# RPi-HAT_BUS-Controller_V0_3.net
KiCad netlist of a schematic drawn in EAGLE
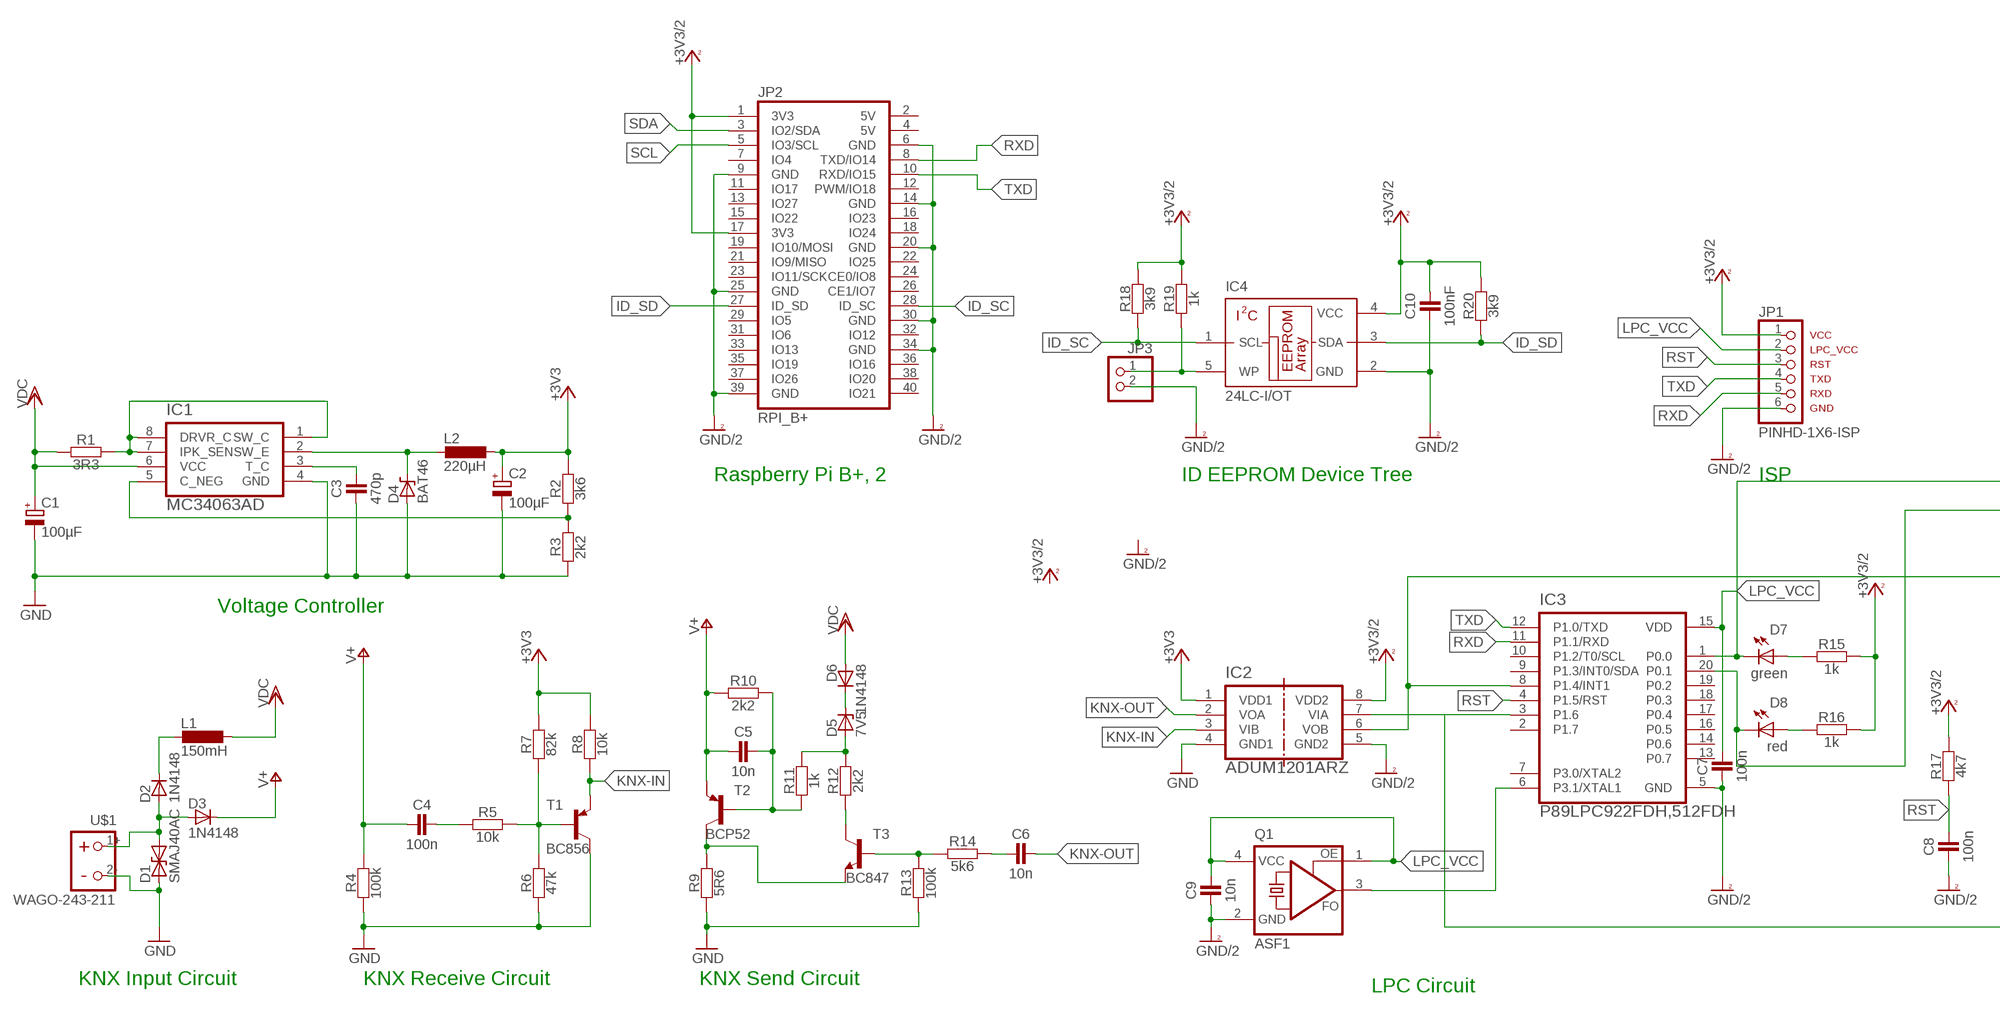
[diagram p0: schematic, sheet 1, part 1 of 2]
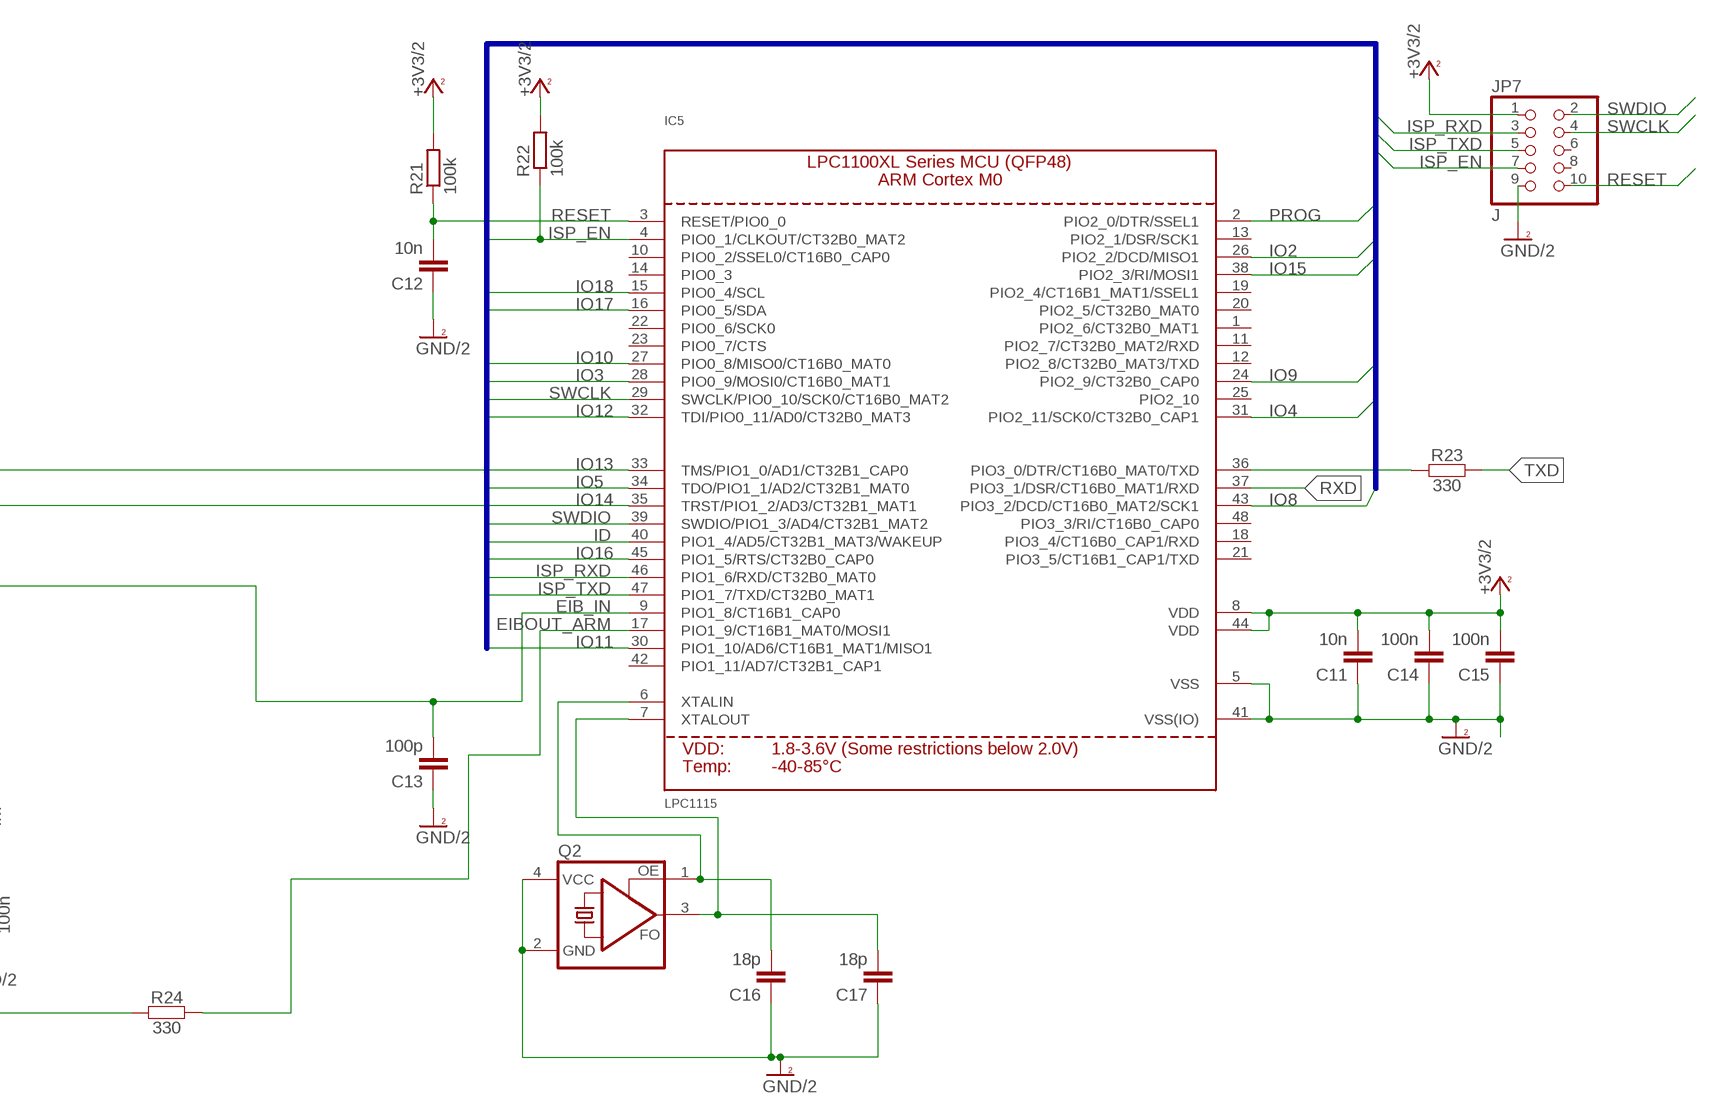
[diagram p1: schematic, sheet 1, part 2 of 2]

(export (version "E")
  (design (tool "Eeschema 10.0.6"))
  (components
    (comp (ref "C1")
      (value "100µF")
      (footprint "eagle-import:PANASONIC_D")
      (libsource (lib "eagle-import") (part "100µF,35V"))
    )
    (comp (ref "C2")
      (value "100µF")
      (footprint "eagle-import:PANASONIC_C")
      (libsource (lib "eagle-import") (part "100µF,6.3V"))
    )
    (comp (ref "C3")
      (value "470p")
      (footprint "eagle-import:R1206")
      (libsource (lib "eagle-import") (part "CAPACITORC1206"))
    )
    (comp (ref "C4")
      (value "100n")
      (footprint "eagle-import:R1206")
      (libsource (lib "eagle-import") (part "CAPACITORC1206"))
    )
    (comp (ref "C5")
      (value "10n")
      (footprint "eagle-import:R1206")
      (libsource (lib "eagle-import") (part "CAPACITORC1206"))
    )
    (comp (ref "C6")
      (value "10n")
      (footprint "eagle-import:R1206")
      (libsource (lib "eagle-import") (part "CAPACITORC1206"))
    )
    (comp (ref "C7")
      (value "100n")
      (footprint "eagle-import:R1206")
      (libsource (lib "eagle-import") (part "CAPACITORC1206"))
    )
    (comp (ref "C8")
      (value "100n")
      (footprint "eagle-import:R1206")
      (libsource (lib "eagle-import") (part "CAPACITORC1206"))
    )
    (comp (ref "C9")
      (value "10n")
      (footprint "eagle-import:R1206")
      (libsource (lib "eagle-import") (part "CAPACITORC1206"))
    )
    (comp (ref "C10")
      (value "100nF")
      (footprint "eagle-import:R1206")
      (libsource (lib "eagle-import") (part "CAPACITORC1206"))
    )
    (comp (ref "C11")
      (value "10n")
      (footprint "eagle-import:C1206")
      (libsource (lib "eagle-import") (part "C-EUC1206"))
    )
    (comp (ref "C12")
      (value "10n")
      (footprint "eagle-import:C1206")
      (libsource (lib "eagle-import") (part "C-EUC1206"))
    )
    (comp (ref "C13")
      (value "100p")
      (footprint "eagle-import:C1206")
      (libsource (lib "eagle-import") (part "C-EUC1206"))
    )
    (comp (ref "C14")
      (value "100n")
      (footprint "eagle-import:C1206")
      (libsource (lib "eagle-import") (part "C-EUC1206"))
    )
    (comp (ref "C15")
      (value "100n")
      (footprint "eagle-import:C1206")
      (libsource (lib "eagle-import") (part "C-EUC1206"))
    )
    (comp (ref "C16")
      (value "18p")
      (footprint "eagle-import:C1206")
      (libsource (lib "eagle-import") (part "C-EUC1206"))
    )
    (comp (ref "C17")
      (value "18p")
      (footprint "eagle-import:C1206")
      (libsource (lib "eagle-import") (part "C-EUC1206"))
    )
    (comp (ref "D1")
      (value "SMAJ40AC")
      (footprint "eagle-import:DO-214AC")
      (libsource (lib "eagle-import") (part "SMAJ40AC"))
    )
    (comp (ref "D2")
      (value "1N4148")
      (footprint "eagle-import:MINIMELF")
      (libsource (lib "eagle-import") (part "1N4148MINIMELF"))
    )
    (comp (ref "D3")
      (value "1N4148")
      (footprint "eagle-import:MINIMELF")
      (libsource (lib "eagle-import") (part "1N4148MINIMELF"))
    )
    (comp (ref "D4")
      (value "BAT46")
      (footprint "eagle-import:MINIMELF")
      (libsource (lib "eagle-import") (part "BAT46"))
    )
    (comp (ref "D5")
      (value "7V5")
      (footprint "eagle-import:MINIMELF")
      (libsource (lib "eagle-import") (part "Z-DIODE"))
    )
    (comp (ref "D6")
      (value "1N4148")
      (footprint "eagle-import:MINIMELF")
      (libsource (lib "eagle-import") (part "Diode_for_Selfbus-Projects_1N4148MINIMELF"))
    )
    (comp (ref "D7")
      (value "green")
      (footprint "eagle-import:CHIPLED_1206")
      (libsource (lib "eagle-import") (part "LED1206"))
    )
    (comp (ref "D8")
      (value "red")
      (footprint "eagle-import:CHIPLED_1206")
      (libsource (lib "eagle-import") (part "LED1206"))
    )
    (comp (ref "IC1")
      (value "MC34063AD")
      (footprint "eagle-import:SOIC127P600X175-8N")
      (libsource (lib "eagle-import") (part "MC34063AD"))
    )
    (comp (ref "IC2")
      (value "ADUM1201ARZ")
      (footprint "eagle-import:SOIC127P600X175-8N")
      (libsource (lib "eagle-import") (part "ADUM1201ARZ"))
    )
    (comp (ref "IC3")
      (value "P89LPC922FDH,512FDH")
      (footprint "eagle-import:SOP65P640X110-20N")
      (fields (field (name "MPN") "P89LPC922FDH,512"))
      (libsource (lib "eagle-import") (part "P89LPC922FDH,512FDH"))
    )
    (comp (ref "IC4")
      (value "24LC-I/OT")
      (footprint "eagle-import:SOT23-5")
      (libsource (lib "eagle-import") (part "24LC-I/OT"))
    )
    (comp (ref "IC5")
      (value "LPC1115")
      (footprint "eagle-import:LQFP48")
      (libsource (lib "eagle-import") (part "LPC1113/4/5_QFP48_XLSERIES"))
    )
    (comp (ref "JP1")
      (value "PINHD-1X6-ISP")
      (footprint "eagle-import:1X06")
      (libsource (lib "eagle-import") (part "PINHD-1X6-ISP"))
    )
    (comp (ref "JP2")
      (value "RPI_B+")
      (footprint "eagle-import:RPI-B+HAT")
      (libsource (lib "eagle-import") (part "RPI_B+"))
    )
    (comp (ref "JP3")
      (value "PINHD-1X2")
      (footprint "eagle-import:1X02")
      (libsource (lib "eagle-import") (part "PINHD-1X2"))
    )
    (comp (ref "JP7")
      (value "J")
      (footprint "eagle-import:2X05M")
      (libsource (lib "eagle-import") (part "PINHD-2X05_2.00"))
    )
    (comp (ref "L1")
      (value "150mH")
      (footprint "eagle-import:11P-L1")
      (libsource (lib "eagle-import") (part "150MH-L11PL1"))
    )
    (comp (ref "L2")
      (value "220µH")
      (footprint "eagle-import:2200-11.43")
      (libsource (lib "eagle-import") (part "220µH-SMCC11.43"))
    )
    (comp (ref "Q1")
      (value "ASF1")
      (footprint "eagle-import:ASF")
      (libsource (lib "eagle-import") (part "ASF1"))
    )
    (comp (ref "Q2")
      (value "ASFL")
      (footprint "eagle-import:ASF")
      (libsource (lib "eagle-import") (part "crystal_ASFL"))
    )
    (comp (ref "R1")
      (value "3R3")
      (footprint "eagle-import:R1206")
      (libsource (lib "eagle-import") (part "RESISTORR1206"))
    )
    (comp (ref "R2")
      (value "3k6")
      (footprint "eagle-import:R1206")
      (libsource (lib "eagle-import") (part "RESISTORR1206"))
    )
    (comp (ref "R3")
      (value "2k2")
      (footprint "eagle-import:R1206")
      (libsource (lib "eagle-import") (part "RESISTORR1206"))
    )
    (comp (ref "R4")
      (value "100k")
      (footprint "eagle-import:R1206")
      (libsource (lib "eagle-import") (part "RESISTORR1206"))
    )
    (comp (ref "R5")
      (value "10k")
      (footprint "eagle-import:R1206")
      (libsource (lib "eagle-import") (part "RESISTORR1206"))
    )
    (comp (ref "R6")
      (value "47k")
      (footprint "eagle-import:R1206")
      (libsource (lib "eagle-import") (part "RESISTORR1206"))
    )
    (comp (ref "R7")
      (value "82k")
      (footprint "eagle-import:R1206")
      (libsource (lib "eagle-import") (part "RESISTORR1206"))
    )
    (comp (ref "R8")
      (value "10k")
      (footprint "eagle-import:R1206")
      (libsource (lib "eagle-import") (part "RESISTORR1206"))
    )
    (comp (ref "R9")
      (value "5R6")
      (footprint "eagle-import:R1206")
      (libsource (lib "eagle-import") (part "RESISTORR1206"))
    )
    (comp (ref "R10")
      (value "2k2")
      (footprint "eagle-import:R1206")
      (libsource (lib "eagle-import") (part "RESISTORR1206"))
    )
    (comp (ref "R11")
      (value "1k")
      (footprint "eagle-import:R1206")
      (libsource (lib "eagle-import") (part "RESISTORR1206"))
    )
    (comp (ref "R12")
      (value "2k2")
      (footprint "eagle-import:R1206")
      (libsource (lib "eagle-import") (part "RESISTORR1206"))
    )
    (comp (ref "R13")
      (value "100k")
      (footprint "eagle-import:R1206")
      (libsource (lib "eagle-import") (part "RESISTORR1206"))
    )
    (comp (ref "R14")
      (value "5k6")
      (footprint "eagle-import:R1206")
      (libsource (lib "eagle-import") (part "RESISTORR1206"))
    )
    (comp (ref "R15")
      (value "1k")
      (footprint "eagle-import:R1206")
      (libsource (lib "eagle-import") (part "RESISTORR1206"))
    )
    (comp (ref "R16")
      (value "1k")
      (footprint "eagle-import:R1206")
      (libsource (lib "eagle-import") (part "RESISTORR1206"))
    )
    (comp (ref "R17")
      (value "4k7")
      (footprint "eagle-import:R1206")
      (libsource (lib "eagle-import") (part "RESISTORR1206"))
    )
    (comp (ref "R18")
      (value "3k9")
      (footprint "eagle-import:R1206")
      (libsource (lib "eagle-import") (part "RESISTORR1206"))
    )
    (comp (ref "R19")
      (value "1k")
      (footprint "eagle-import:R1206")
      (libsource (lib "eagle-import") (part "RESISTORR1206"))
    )
    (comp (ref "R20")
      (value "3k9")
      (footprint "eagle-import:R1206")
      (libsource (lib "eagle-import") (part "RESISTORR1206"))
    )
    (comp (ref "R21")
      (value "100k")
      (footprint "eagle-import:R1206")
      (libsource (lib "eagle-import") (part "R-EU_R1206"))
    )
    (comp (ref "R22")
      (value "100k")
      (footprint "eagle-import:R1206")
      (libsource (lib "eagle-import") (part "R-EU_R1206"))
    )
    (comp (ref "R23")
      (value "330")
      (footprint "eagle-import:R1206")
      (libsource (lib "eagle-import") (part "RESISTORR1206"))
    )
    (comp (ref "R24")
      (value "330")
      (footprint "eagle-import:R1206")
      (libsource (lib "eagle-import") (part "RESISTORR1206"))
    )
    (comp (ref "T1")
      (value "BC856")
      (footprint "eagle-import:SOT23")
      (libsource (lib "eagle-import") (part "PNPBC856"))
    )
    (comp (ref "T2")
      (value "BCP52")
      (footprint "eagle-import:SOT223")
      (libsource (lib "eagle-import") (part "PNPBCP52"))
    )
    (comp (ref "T3")
      (value "BC847")
      (footprint "eagle-import:SOT23")
      (libsource (lib "eagle-import") (part "NPN-BC847"))
    )
    (comp (ref "U$1")
      (value "WAGO-243-211")
      (footprint "eagle-import:WAGO-243-211")
      (libsource (lib "eagle-import") (part "WAGO-243-211"))
    )
  )
  (nets
    (net (code "1") (name "+3V3") (class "Default")
      (node (ref "C2") (pin "+") (pinfunction "+_+") (pintype "passive"))
      (node (ref "IC2") (pin "1") (pinfunction "VDD1_1") (pintype "power_in"))
      (node (ref "L2") (pin "1") (pinfunction "1_1") (pintype "passive"))
      (node (ref "R2") (pin "2") (pinfunction "2_2") (pintype "passive"))
      (node (ref "R7") (pin "2") (pinfunction "2_2") (pintype "passive"))
      (node (ref "R8") (pin "2") (pinfunction "2_2") (pintype "passive"))
    )
    (net (code "2") (name "+3V3{slash}2") (class "Default")
      (node (ref "C10") (pin "2") (pinfunction "2_2") (pintype "passive"))
      (node (ref "C11") (pin "2") (pinfunction "2_2") (pintype "passive"))
      (node (ref "C14") (pin "2") (pinfunction "2_2") (pintype "passive"))
      (node (ref "C15") (pin "2") (pinfunction "2_2") (pintype "passive"))
      (node (ref "IC2") (pin "8") (pinfunction "VDD2_8") (pintype "power_in"))
      (node (ref "IC4") (pin "4") (pinfunction "VCC_4") (pintype "power_in"))
      (node (ref "IC5") (pin "44") (pinfunction "VDD_44") (pintype "power_in"))
      (node (ref "IC5") (pin "8") (pinfunction "VDD_8") (pintype "power_in"))
      (node (ref "JP1") (pin "1") (pinfunction "1_1") (pintype "passive"))
      (node (ref "JP2") (pin "1") (pinfunction "3V3_1") (pintype "passive"))
      (node (ref "JP2") (pin "17") (pinfunction "3V3_17") (pintype "passive"))
      (node (ref "JP7") (pin "1") (pinfunction "1_1") (pintype "passive"))
      (node (ref "R15") (pin "2") (pinfunction "2_2") (pintype "passive"))
      (node (ref "R16") (pin "2") (pinfunction "2_2") (pintype "passive"))
      (node (ref "R17") (pin "2") (pinfunction "2_2") (pintype "passive"))
      (node (ref "R18") (pin "2") (pinfunction "2_2") (pintype "passive"))
      (node (ref "R19") (pin "2") (pinfunction "2_2") (pintype "passive"))
      (node (ref "R20") (pin "2") (pinfunction "2_2") (pintype "passive"))
      (node (ref "R21") (pin "2") (pinfunction "2_2") (pintype "passive"))
      (node (ref "R22") (pin "2") (pinfunction "2_2") (pintype "passive"))
    )
    (net (code "3") (name "/EIBOUT_ARM") (class "Default")
      (node (ref "IC5") (pin "17") (pinfunction "PIO1_9/CT16B1_MAT0/MOSI1_17") (pintype "bidirectional"))
      (node (ref "R24") (pin "2") (pinfunction "2_2") (pintype "passive"))
    )
    (net (code "4") (name "/EIB_IN") (class "Default")
      (node (ref "C13") (pin "2") (pinfunction "2_2") (pintype "passive"))
      (node (ref "IC2") (pin "6") (pinfunction "VOB_6") (pintype "output"))
      (node (ref "IC3") (pin "8") (pinfunction "P1.4/INT1_8") (pintype "bidirectional"))
      (node (ref "IC5") (pin "9") (pinfunction "PIO1_8/CT16B1_CAP0_9") (pintype "bidirectional"))
    )
    (net (code "5") (name "/ID") (class "Default")
      (node (ref "IC5") (pin "40") (pinfunction "PIO1_4/AD5/CT32B1_MAT3/WAKEUP_40") (pintype "bidirectional"))
    )
    (net (code "6") (name "/IO2") (class "Default")
      (node (ref "IC5") (pin "26") (pinfunction "PIO2_2/DCD/MISO1_26") (pintype "bidirectional"))
    )
    (net (code "7") (name "/IO3") (class "Default")
      (node (ref "IC5") (pin "28") (pinfunction "PIO0_9/MOSI0/CT16B0_MAT1_28") (pintype "bidirectional"))
    )
    (net (code "8") (name "/IO4") (class "Default")
      (node (ref "IC5") (pin "31") (pinfunction "PIO2_11/SCK0/CT32B0_CAP1_31") (pintype "bidirectional"))
    )
    (net (code "9") (name "/IO5") (class "Default")
      (node (ref "IC5") (pin "34") (pinfunction "TDO/PIO1_1/AD2/CT32B1_MAT0_34") (pintype "bidirectional"))
    )
    (net (code "10") (name "/IO8") (class "Default")
      (node (ref "IC5") (pin "43") (pinfunction "PIO3_2/DCD/CT16B0_MAT2/SCK1_43") (pintype "bidirectional"))
    )
    (net (code "11") (name "/IO9") (class "Default")
      (node (ref "IC5") (pin "24") (pinfunction "PIO2_9/CT32B0_CAP0_24") (pintype "bidirectional"))
    )
    (net (code "12") (name "/IO10") (class "Default")
      (node (ref "IC5") (pin "27") (pinfunction "PIO0_8/MISO0/CT16B0_MAT0_27") (pintype "bidirectional"))
    )
    (net (code "13") (name "/IO11") (class "Default")
      (node (ref "IC5") (pin "30") (pinfunction "PIO1_10/AD6/CT16B1_MAT1/MISO1_30") (pintype "bidirectional"))
    )
    (net (code "14") (name "/IO12") (class "Default")
      (node (ref "D8") (pin "C") (pinfunction "C_C") (pintype "passive"))
      (node (ref "IC3") (pin "20") (pinfunction "P0.1_20") (pintype "bidirectional"))
      (node (ref "IC5") (pin "32") (pinfunction "TDI/PIO0_11/AD0/CT32B0_MAT3_32") (pintype "bidirectional"))
    )
    (net (code "15") (name "/IO13") (class "Default")
      (node (ref "IC5") (pin "33") (pinfunction "TMS/PIO1_0/AD1/CT32B1_CAP0_33") (pintype "bidirectional"))
    )
    (net (code "16") (name "/IO14") (class "Default")
      (node (ref "IC5") (pin "35") (pinfunction "TRST/PIO1_2/AD3/CT32B1_MAT1_35") (pintype "bidirectional"))
    )
    (net (code "17") (name "/IO15") (class "Default")
      (node (ref "D7") (pin "C") (pinfunction "C_C") (pintype "passive"))
      (node (ref "IC3") (pin "1") (pinfunction "P0.0_1") (pintype "bidirectional"))
      (node (ref "IC5") (pin "38") (pinfunction "PIO2_3/RI/MOSI1_38") (pintype "bidirectional"))
    )
    (net (code "18") (name "/IO16") (class "Default")
      (node (ref "IC5") (pin "45") (pinfunction "PIO1_5/RTS/CT32B0_CAP0_45") (pintype "bidirectional"))
    )
    (net (code "19") (name "/IO17") (class "Default")
      (node (ref "IC5") (pin "16") (pinfunction "PIO0_5/SDA_16") (pintype "bidirectional"))
    )
    (net (code "20") (name "/IO18") (class "Default")
      (node (ref "IC5") (pin "15") (pinfunction "PIO0_4/SCL_15") (pintype "bidirectional"))
    )
    (net (code "21") (name "/ISP_EN") (class "Default")
      (node (ref "IC5") (pin "4") (pinfunction "PIO0_1/CLKOUT/CT32B0_MAT2_4") (pintype "bidirectional"))
      (node (ref "JP7") (pin "7") (pinfunction "7_7") (pintype "passive"))
      (node (ref "R22") (pin "1") (pinfunction "1_1") (pintype "passive"))
    )
    (net (code "22") (name "/ISP_RXD") (class "Default")
      (node (ref "IC5") (pin "46") (pinfunction "PIO1_6/RXD/CT32B0_MAT0_46") (pintype "bidirectional"))
      (node (ref "JP7") (pin "3") (pinfunction "3_3") (pintype "passive"))
    )
    (net (code "23") (name "/ISP_TXD") (class "Default")
      (node (ref "IC5") (pin "47") (pinfunction "PIO1_7/TXD/CT32B0_MAT1_47") (pintype "bidirectional"))
      (node (ref "JP7") (pin "5") (pinfunction "5_5") (pintype "passive"))
    )
    (net (code "24") (name "/PROG") (class "Default")
      (node (ref "IC5") (pin "2") (pinfunction "PIO2_0/DTR/SSEL1_2") (pintype "bidirectional"))
    )
    (net (code "25") (name "/RESET") (class "Default")
      (node (ref "C12") (pin "2") (pinfunction "2_2") (pintype "passive"))
      (node (ref "IC5") (pin "3") (pinfunction "RESET/PIO0_0_3") (pintype "bidirectional"))
      (node (ref "JP7") (pin "10") (pinfunction "10_10") (pintype "passive"))
      (node (ref "R21") (pin "1") (pinfunction "1_1") (pintype "passive"))
    )
    (net (code "26") (name "/SWCLK") (class "Default")
      (node (ref "IC5") (pin "29") (pinfunction "SWCLK/PIO0_10/SCK0/CT16B0_MAT2_29") (pintype "bidirectional"))
      (node (ref "JP7") (pin "4") (pinfunction "4_4") (pintype "passive"))
    )
    (net (code "27") (name "/SWDIO") (class "Default")
      (node (ref "IC5") (pin "39") (pinfunction "SWDIO/PIO1_3/AD4/CT32B1_MAT2_39") (pintype "bidirectional"))
      (node (ref "JP7") (pin "2") (pinfunction "2_2") (pintype "passive"))
    )
    (net (code "28") (name "GND") (class "Default")
      (node (ref "C1") (pin "-") (pinfunction "-_-") (pintype "passive"))
      (node (ref "C2") (pin "-") (pinfunction "-_-") (pintype "passive"))
      (node (ref "C3") (pin "1") (pinfunction "1_1") (pintype "passive"))
      (node (ref "D1") (pin "A") (pinfunction "A_A") (pintype "passive"))
      (node (ref "D4") (pin "A") (pinfunction "A_A") (pintype "passive"))
      (node (ref "IC1") (pin "4") (pinfunction "GND_4") (pintype "passive"))
      (node (ref "IC2") (pin "4") (pinfunction "GND1_4") (pintype "passive"))
      (node (ref "R13") (pin "1") (pinfunction "1_1") (pintype "passive"))
      (node (ref "R3") (pin "1") (pinfunction "1_1") (pintype "passive"))
      (node (ref "R4") (pin "1") (pinfunction "1_1") (pintype "passive"))
      (node (ref "R6") (pin "1") (pinfunction "1_1") (pintype "passive"))
      (node (ref "R9") (pin "1") (pinfunction "1_1") (pintype "passive"))
      (node (ref "T1") (pin "3") (pinfunction "C_3") (pintype "passive"))
      (node (ref "U$1") (pin "2-") (pinfunction "2-_2-") (pintype "passive"))
    )
    (net (code "29") (name "GND{slash}2") (class "Default")
      (node (ref "C10") (pin "1") (pinfunction "1_1") (pintype "passive"))
      (node (ref "C11") (pin "1") (pinfunction "1_1") (pintype "passive"))
      (node (ref "C12") (pin "1") (pinfunction "1_1") (pintype "passive"))
      (node (ref "C13") (pin "1") (pinfunction "1_1") (pintype "passive"))
      (node (ref "C14") (pin "1") (pinfunction "1_1") (pintype "passive"))
      (node (ref "C15") (pin "1") (pinfunction "1_1") (pintype "passive"))
      (node (ref "C16") (pin "1") (pinfunction "1_1") (pintype "passive"))
      (node (ref "C17") (pin "1") (pinfunction "1_1") (pintype "passive"))
      (node (ref "C7") (pin "1") (pinfunction "1_1") (pintype "passive"))
      (node (ref "C8") (pin "1") (pinfunction "1_1") (pintype "passive"))
      (node (ref "C9") (pin "1") (pinfunction "1_1") (pintype "passive"))
      (node (ref "IC2") (pin "5") (pinfunction "GND2_5") (pintype "passive"))
      (node (ref "IC3") (pin "5") (pinfunction "GND_5") (pintype "passive"))
      (node (ref "IC4") (pin "2") (pinfunction "GND_2") (pintype "power_in"))
      (node (ref "IC5") (pin "41") (pinfunction "VSS(IO)_41") (pintype "power_in"))
      (node (ref "IC5") (pin "5") (pinfunction "VSS_5") (pintype "power_in"))
      (node (ref "JP1") (pin "6") (pinfunction "6_6") (pintype "passive"))
      (node (ref "JP2") (pin "14") (pinfunction "GND_14") (pintype "passive"))
      (node (ref "JP2") (pin "20") (pinfunction "GND_20") (pintype "passive"))
      (node (ref "JP2") (pin "25") (pinfunction "GND_25") (pintype "passive"))
      (node (ref "JP2") (pin "30") (pinfunction "GND_30") (pintype "bidirectional"))
      (node (ref "JP2") (pin "34") (pinfunction "GND_34") (pintype "bidirectional"))
      (node (ref "JP2") (pin "39") (pinfunction "GND_39") (pintype "bidirectional"))
      (node (ref "JP2") (pin "6") (pinfunction "GND_6") (pintype "passive"))
      (node (ref "JP2") (pin "9") (pinfunction "GND_9") (pintype "passive"))
      (node (ref "JP3") (pin "2") (pinfunction "2_2") (pintype "passive"))
      (node (ref "JP7") (pin "9") (pinfunction "9_9") (pintype "passive"))
      (node (ref "Q1") (pin "2") (pinfunction "GND_2") (pintype "power_in"))
      (node (ref "Q2") (pin "2") (pinfunction "GND_2") (pintype "power_in"))
      (node (ref "Q2") (pin "4") (pinfunction "VCC_4") (pintype "power_in"))
    )
    (net (code "30") (name "ID_SC") (class "Default")
      (node (ref "IC4") (pin "1") (pinfunction "SCL_1") (pintype "bidirectional"))
      (node (ref "JP2") (pin "28") (pinfunction "ID_SC_28") (pintype "bidirectional"))
      (node (ref "R18") (pin "1") (pinfunction "1_1") (pintype "passive"))
    )
    (net (code "31") (name "ID_SD") (class "Default")
      (node (ref "IC4") (pin "3") (pinfunction "SDA_3") (pintype "bidirectional"))
      (node (ref "JP2") (pin "27") (pinfunction "ID_SD_27") (pintype "bidirectional"))
      (node (ref "R20") (pin "1") (pinfunction "1_1") (pintype "passive"))
    )
    (net (code "32") (name "KNX-IN") (class "Default")
      (node (ref "IC2") (pin "3") (pinfunction "VIB_3") (pintype "input"))
      (node (ref "R8") (pin "1") (pinfunction "1_1") (pintype "passive"))
      (node (ref "T1") (pin "2") (pinfunction "E_2") (pintype "passive"))
    )
    (net (code "33") (name "KNX-OUT") (class "Default")
      (node (ref "C6") (pin "2") (pinfunction "2_2") (pintype "passive"))
      (node (ref "IC2") (pin "2") (pinfunction "VOA_2") (pintype "output"))
    )
    (net (code "34") (name "LPC_VCC") (class "Default")
      (node (ref "C7") (pin "2") (pinfunction "2_2") (pintype "passive"))
      (node (ref "C9") (pin "2") (pinfunction "2_2") (pintype "passive"))
      (node (ref "IC3") (pin "15") (pinfunction "VDD_15") (pintype "power_in"))
      (node (ref "JP1") (pin "2") (pinfunction "2_2") (pintype "passive"))
      (node (ref "Q1") (pin "1") (pinfunction "OE_1") (pintype "input"))
      (node (ref "Q1") (pin "4") (pinfunction "VCC_4") (pintype "power_in"))
    )
    (net (code "35") (name "Net-(C4-Pad2)") (class "Default")
      (node (ref "C4") (pin "2") (pinfunction "2_2") (pintype "passive"))
      (node (ref "R5") (pin "1") (pinfunction "1_1") (pintype "passive"))
    )
    (net (code "36") (name "Net-(C6-Pad1)") (class "Default")
      (node (ref "C6") (pin "1") (pinfunction "1_1") (pintype "passive"))
      (node (ref "R14") (pin "2") (pinfunction "2_2") (pintype "passive"))
    )
    (net (code "37") (name "Net-(D1-PadC)") (class "Default")
      (node (ref "D1") (pin "C") (pinfunction "C_C") (pintype "passive"))
      (node (ref "D2") (pin "A") (pinfunction "A_A") (pintype "passive"))
      (node (ref "D3") (pin "A") (pinfunction "A_A") (pintype "passive"))
      (node (ref "U$1") (pin "1+") (pinfunction "1+_1+") (pintype "passive"))
    )
    (net (code "38") (name "Net-(D2-PadC)") (class "Default")
      (node (ref "D2") (pin "C") (pinfunction "C_C") (pintype "passive"))
      (node (ref "L1") (pin "2") (pinfunction "2_2") (pintype "passive"))
    )
    (net (code "39") (name "Net-(D5-PadA)") (class "Default")
      (node (ref "D5") (pin "A") (pinfunction "A_A") (pintype "passive"))
      (node (ref "R11") (pin "2") (pinfunction "2_2") (pintype "passive"))
      (node (ref "R12") (pin "2") (pinfunction "2_2") (pintype "passive"))
    )
    (net (code "40") (name "Net-(D5-PadC)") (class "Default")
      (node (ref "D5") (pin "C") (pinfunction "C_C") (pintype "passive"))
      (node (ref "D6") (pin "C") (pinfunction "C_C") (pintype "passive"))
    )
    (net (code "41") (name "Net-(D7-PadA)") (class "Default")
      (node (ref "D7") (pin "A") (pinfunction "A_A") (pintype "passive"))
      (node (ref "R15") (pin "1") (pinfunction "1_1") (pintype "passive"))
    )
    (net (code "42") (name "Net-(D8-PadA)") (class "Default")
      (node (ref "D8") (pin "A") (pinfunction "A_A") (pintype "passive"))
      (node (ref "R16") (pin "1") (pinfunction "1_1") (pintype "passive"))
    )
    (net (code "43") (name "Net-(IC1-C_NEG)") (class "Default")
      (node (ref "IC1") (pin "5") (pinfunction "C_NEG_5") (pintype "input"))
      (node (ref "R2") (pin "1") (pinfunction "1_1") (pintype "passive"))
      (node (ref "R3") (pin "2") (pinfunction "2_2") (pintype "passive"))
    )
    (net (code "44") (name "Net-(IC1-DRVR_C)") (class "Default")
      (node (ref "IC1") (pin "1") (pinfunction "SW_C_1") (pintype "output"))
      (node (ref "IC1") (pin "7") (pinfunction "IPK_SEN_7") (pintype "input"))
      (node (ref "IC1") (pin "8") (pinfunction "DRVR_C_8") (pintype "input"))
      (node (ref "R1") (pin "2") (pinfunction "2_2") (pintype "passive"))
    )
    (net (code "45") (name "Net-(IC1-SW_E)") (class "Default")
      (node (ref "D4") (pin "C") (pinfunction "C_C") (pintype "passive"))
      (node (ref "IC1") (pin "2") (pinfunction "SW_E_2") (pintype "output"))
      (node (ref "L2") (pin "2") (pinfunction "2_2") (pintype "passive"))
    )
    (net (code "46") (name "Net-(IC1-T_C)") (class "Default")
      (node (ref "C3") (pin "2") (pinfunction "2_2") (pintype "passive"))
      (node (ref "IC1") (pin "3") (pinfunction "T_C_3") (pintype "output"))
    )
    (net (code "47") (name "Net-(IC2-VIA)") (class "Default")
      (node (ref "IC2") (pin "7") (pinfunction "VIA_7") (pintype "input"))
      (node (ref "IC3") (pin "3") (pinfunction "P1.6_3") (pintype "bidirectional"))
      (node (ref "R24") (pin "1") (pinfunction "1_1") (pintype "passive"))
    )
    (net (code "48") (name "Net-(IC3-P3.1{slash}XTAL1)") (class "Default")
      (node (ref "IC3") (pin "6") (pinfunction "P3.1/XTAL1_6") (pintype "bidirectional"))
      (node (ref "Q1") (pin "3") (pinfunction "FO_3") (pintype "output"))
    )
    (net (code "49") (name "Net-(IC4-WP)") (class "Default")
      (node (ref "IC4") (pin "5") (pinfunction "WP_5") (pintype "bidirectional"))
      (node (ref "JP3") (pin "1") (pinfunction "1_1") (pintype "passive"))
      (node (ref "R19") (pin "1") (pinfunction "1_1") (pintype "passive"))
    )
    (net (code "50") (name "Net-(IC5-PIO3_0{slash}DTR{slash}CT16B0_MAT0{slash}TXD)") (class "Default")
      (node (ref "IC5") (pin "36") (pinfunction "PIO3_0/DTR/CT16B0_MAT0/TXD_36") (pintype "bidirectional"))
      (node (ref "R23") (pin "1") (pinfunction "1_1") (pintype "passive"))
    )
    (net (code "51") (name "Net-(IC5-XTALIN)") (class "Default")
      (node (ref "C16") (pin "2") (pinfunction "2_2") (pintype "passive"))
      (node (ref "IC5") (pin "6") (pinfunction "XTALIN_6") (pintype "input"))
      (node (ref "Q2") (pin "1") (pinfunction "OE_1") (pintype "input"))
    )
    (net (code "52") (name "Net-(IC5-XTALOUT)") (class "Default")
      (node (ref "C17") (pin "2") (pinfunction "2_2") (pintype "passive"))
      (node (ref "IC5") (pin "7") (pinfunction "XTALOUT_7") (pintype "output"))
      (node (ref "Q2") (pin "3") (pinfunction "FO_3") (pintype "output"))
    )
    (net (code "53") (name "Net-(T1-B)") (class "Default")
      (node (ref "R5") (pin "2") (pinfunction "2_2") (pintype "passive"))
      (node (ref "R6") (pin "2") (pinfunction "2_2") (pintype "passive"))
      (node (ref "R7") (pin "1") (pinfunction "1_1") (pintype "passive"))
      (node (ref "T1") (pin "1") (pinfunction "B_1") (pintype "passive"))
    )
    (net (code "54") (name "Net-(T2-B)") (class "Default")
      (node (ref "C5") (pin "2") (pinfunction "2_2") (pintype "passive"))
      (node (ref "R10") (pin "2") (pinfunction "2_2") (pintype "passive"))
      (node (ref "R11") (pin "1") (pinfunction "1_1") (pintype "passive"))
      (node (ref "T2") (pin "1") (pinfunction "B_1") (pintype "passive"))
    )
    (net (code "55") (name "Net-(T3-B)") (class "Default")
      (node (ref "R13") (pin "2") (pinfunction "2_2") (pintype "passive"))
      (node (ref "R14") (pin "1") (pinfunction "1_1") (pintype "passive"))
      (node (ref "T3") (pin "1") (pinfunction "B_1") (pintype "passive"))
    )
    (net (code "56") (name "Net-(T3-C)") (class "Default")
      (node (ref "R12") (pin "1") (pinfunction "1_1") (pintype "passive"))
      (node (ref "T3") (pin "3") (pinfunction "C_3") (pintype "passive"))
    )
    (net (code "57") (name "Net-(T3-E)") (class "Default")
      (node (ref "R9") (pin "2") (pinfunction "2_2") (pintype "passive"))
      (node (ref "T2") (pin "2") (pinfunction "C_2") (pintype "passive"))
      (node (ref "T2") (pin "4") (pinfunction "C_4") (pintype "passive"))
      (node (ref "T3") (pin "2") (pinfunction "E_2") (pintype "passive"))
    )
    (net (code "58") (name "RST") (class "Default")
      (node (ref "C8") (pin "2") (pinfunction "2_2") (pintype "passive"))
      (node (ref "IC3") (pin "4") (pinfunction "P1.5/RST_4") (pintype "input"))
      (node (ref "JP1") (pin "3") (pinfunction "3_3") (pintype "passive"))
      (node (ref "R17") (pin "1") (pinfunction "1_1") (pintype "passive"))
    )
    (net (code "59") (name "RXD") (class "Default")
      (node (ref "IC3") (pin "11") (pinfunction "P1.1/RXD_11") (pintype "bidirectional"))
      (node (ref "IC5") (pin "37") (pinfunction "PIO3_1/DSR/CT16B0_MAT1/RXD_37") (pintype "bidirectional"))
      (node (ref "JP1") (pin "5") (pinfunction "5_5") (pintype "passive"))
      (node (ref "JP2") (pin "8") (pinfunction "TXD/IO14_8") (pintype "passive"))
    )
    (net (code "60") (name "SCL") (class "Default")
      (node (ref "JP2") (pin "5") (pinfunction "IO3/SCL_5") (pintype "passive"))
    )
    (net (code "61") (name "SDA") (class "Default")
      (node (ref "JP2") (pin "3") (pinfunction "IO2/SDA_3") (pintype "passive"))
    )
    (net (code "62") (name "TXD") (class "Default")
      (node (ref "IC3") (pin "12") (pinfunction "P1.0/TXD_12") (pintype "bidirectional"))
      (node (ref "JP1") (pin "4") (pinfunction "4_4") (pintype "passive"))
      (node (ref "JP2") (pin "10") (pinfunction "RXD/IO15_10") (pintype "passive"))
      (node (ref "R23") (pin "2") (pinfunction "2_2") (pintype "passive"))
    )
    (net (code "63") (name "V+") (class "Default")
      (node (ref "C4") (pin "1") (pinfunction "1_1") (pintype "passive"))
      (node (ref "C5") (pin "1") (pinfunction "1_1") (pintype "passive"))
      (node (ref "D3") (pin "C") (pinfunction "C_C") (pintype "passive"))
      (node (ref "R10") (pin "1") (pinfunction "1_1") (pintype "passive"))
      (node (ref "R4") (pin "2") (pinfunction "2_2") (pintype "passive"))
      (node (ref "T2") (pin "3") (pinfunction "E_3") (pintype "passive"))
    )
    (net (code "64") (name "VDC") (class "Default")
      (node (ref "C1") (pin "+") (pinfunction "+_+") (pintype "passive"))
      (node (ref "D6") (pin "A") (pinfunction "A_A") (pintype "passive"))
      (node (ref "IC1") (pin "6") (pinfunction "VCC_6") (pintype "power_in"))
      (node (ref "L1") (pin "1") (pinfunction "1_1") (pintype "passive"))
      (node (ref "R1") (pin "1") (pinfunction "1_1") (pintype "passive"))
    )
    (net (code "65") (name "unconnected-(IC3-P0.2-Pad19)") (class "Default")
      (node (ref "IC3") (pin "19") (pinfunction "P0.2_19") (pintype "bidirectional"))
    )
    (net (code "66") (name "unconnected-(IC3-P0.3-Pad18)") (class "Default")
      (node (ref "IC3") (pin "18") (pinfunction "P0.3_18") (pintype "bidirectional"))
    )
    (net (code "67") (name "unconnected-(IC3-P0.4-Pad17)") (class "Default")
      (node (ref "IC3") (pin "17") (pinfunction "P0.4_17") (pintype "bidirectional"))
    )
    (net (code "68") (name "unconnected-(IC3-P0.5-Pad16)") (class "Default")
      (node (ref "IC3") (pin "16") (pinfunction "P0.5_16") (pintype "bidirectional"))
    )
    (net (code "69") (name "unconnected-(IC3-P0.6-Pad14)") (class "Default")
      (node (ref "IC3") (pin "14") (pinfunction "P0.6_14") (pintype "bidirectional"))
    )
    (net (code "70") (name "unconnected-(IC3-P0.7-Pad13)") (class "Default")
      (node (ref "IC3") (pin "13") (pinfunction "P0.7_13") (pintype "passive"))
    )
    (net (code "71") (name "unconnected-(IC3-P1.2{slash}T0{slash}SCL-Pad10)") (class "Default")
      (node (ref "IC3") (pin "10") (pinfunction "P1.2/T0/SCL_10") (pintype "bidirectional"))
    )
    (net (code "72") (name "unconnected-(IC3-P1.3{slash}INT0{slash}SDA-Pad9)") (class "Default")
      (node (ref "IC3") (pin "9") (pinfunction "P1.3/INT0/SDA_9") (pintype "bidirectional"))
    )
    (net (code "73") (name "unconnected-(IC3-P1.7-Pad2)") (class "Default")
      (node (ref "IC3") (pin "2") (pinfunction "P1.7_2") (pintype "bidirectional"))
    )
    (net (code "74") (name "unconnected-(IC3-P3.0{slash}XTAL2-Pad7)") (class "Default")
      (node (ref "IC3") (pin "7") (pinfunction "P3.0/XTAL2_7") (pintype "bidirectional"))
    )
    (net (code "75") (name "unconnected-(IC5-PIO0_2{slash}SSEL0{slash}CT16B0_CAP0-Pad10)") (class "Default")
      (node (ref "IC5") (pin "10") (pinfunction "PIO0_2/SSEL0/CT16B0_CAP0_10") (pintype "bidirectional"))
    )
    (net (code "76") (name "unconnected-(IC5-PIO0_3-Pad14)") (class "Default")
      (node (ref "IC5") (pin "14") (pinfunction "PIO0_3_14") (pintype "bidirectional"))
    )
    (net (code "77") (name "unconnected-(IC5-PIO0_6{slash}SCK0-Pad22)") (class "Default")
      (node (ref "IC5") (pin "22") (pinfunction "PIO0_6/SCK0_22") (pintype "bidirectional"))
    )
    (net (code "78") (name "unconnected-(IC5-PIO0_7{slash}CTS-Pad23)") (class "Default")
      (node (ref "IC5") (pin "23") (pinfunction "PIO0_7/CTS_23") (pintype "bidirectional"))
    )
    (net (code "79") (name "unconnected-(IC5-PIO1_11{slash}AD7{slash}CT32B1_CAP1-Pad42)") (class "Default")
      (node (ref "IC5") (pin "42") (pinfunction "PIO1_11/AD7/CT32B1_CAP1_42") (pintype "bidirectional"))
    )
    (net (code "80") (name "unconnected-(IC5-PIO2_1{slash}DSR{slash}SCK1-Pad13)") (class "Default")
      (node (ref "IC5") (pin "13") (pinfunction "PIO2_1/DSR/SCK1_13") (pintype "bidirectional"))
    )
    (net (code "81") (name "unconnected-(IC5-PIO2_4{slash}CT16B1_MAT1{slash}SSEL1-Pad19)") (class "Default")
      (node (ref "IC5") (pin "19") (pinfunction "PIO2_4/CT16B1_MAT1/SSEL1_19") (pintype "bidirectional"))
    )
    (net (code "82") (name "unconnected-(IC5-PIO2_5{slash}CT32B0_MAT0-Pad20)") (class "Default")
      (node (ref "IC5") (pin "20") (pinfunction "PIO2_5/CT32B0_MAT0_20") (pintype "bidirectional"))
    )
    (net (code "83") (name "unconnected-(IC5-PIO2_6{slash}CT32B0_MAT1-Pad1)") (class "Default")
      (node (ref "IC5") (pin "1") (pinfunction "PIO2_6/CT32B0_MAT1_1") (pintype "bidirectional"))
    )
    (net (code "84") (name "unconnected-(IC5-PIO2_7{slash}CT32B0_MAT2{slash}RXD-Pad11)") (class "Default")
      (node (ref "IC5") (pin "11") (pinfunction "PIO2_7/CT32B0_MAT2/RXD_11") (pintype "bidirectional"))
    )
    (net (code "85") (name "unconnected-(IC5-PIO2_8{slash}CT32B0_MAT3{slash}TXD-Pad12)") (class "Default")
      (node (ref "IC5") (pin "12") (pinfunction "PIO2_8/CT32B0_MAT3/TXD_12") (pintype "bidirectional"))
    )
    (net (code "86") (name "unconnected-(IC5-PIO2_10-Pad25)") (class "Default")
      (node (ref "IC5") (pin "25") (pinfunction "PIO2_10_25") (pintype "bidirectional"))
    )
    (net (code "87") (name "unconnected-(IC5-PIO3_3{slash}RI{slash}CT16B0_CAP0-Pad48)") (class "Default")
      (node (ref "IC5") (pin "48") (pinfunction "PIO3_3/RI/CT16B0_CAP0_48") (pintype "bidirectional"))
    )
    (net (code "88") (name "unconnected-(IC5-PIO3_4{slash}CT16B0_CAP1{slash}RXD-Pad18)") (class "Default")
      (node (ref "IC5") (pin "18") (pinfunction "PIO3_4/CT16B0_CAP1/RXD_18") (pintype "bidirectional"))
    )
    (net (code "89") (name "unconnected-(IC5-PIO3_5{slash}CT16B1_CAP1{slash}TXD-Pad21)") (class "Default")
      (node (ref "IC5") (pin "21") (pinfunction "PIO3_5/CT16B1_CAP1/TXD_21") (pintype "bidirectional"))
    )
    (net (code "90") (name "unconnected-(JP2-5V-Pad2)") (class "Default")
      (node (ref "JP2") (pin "2") (pinfunction "5V_2") (pintype "passive"))
    )
    (net (code "91") (name "unconnected-(JP2-5V-Pad4)") (class "Default")
      (node (ref "JP2") (pin "4") (pinfunction "5V_4") (pintype "passive"))
    )
    (net (code "92") (name "unconnected-(JP2-CE0{slash}IO8-Pad24)") (class "Default")
      (node (ref "JP2") (pin "24") (pinfunction "CE0/IO8_24") (pintype "passive"))
    )
    (net (code "93") (name "unconnected-(JP2-CE1{slash}IO7-Pad26)") (class "Default")
      (node (ref "JP2") (pin "26") (pinfunction "CE1/IO7_26") (pintype "passive"))
    )
    (net (code "94") (name "unconnected-(JP2-IO4-Pad7)") (class "Default")
      (node (ref "JP2") (pin "7") (pinfunction "IO4_7") (pintype "passive"))
    )
    (net (code "95") (name "unconnected-(JP2-IO5-Pad29)") (class "Default")
      (node (ref "JP2") (pin "29") (pinfunction "IO5_29") (pintype "bidirectional"))
    )
    (net (code "96") (name "unconnected-(JP2-IO6-Pad31)") (class "Default")
      (node (ref "JP2") (pin "31") (pinfunction "IO6_31") (pintype "bidirectional"))
    )
    (net (code "97") (name "unconnected-(JP2-IO9{slash}MISO-Pad21)") (class "Default")
      (node (ref "JP2") (pin "21") (pinfunction "IO9/MISO_21") (pintype "passive"))
    )
    (net (code "98") (name "unconnected-(JP2-IO10{slash}MOSI-Pad19)") (class "Default")
      (node (ref "JP2") (pin "19") (pinfunction "IO10/MOSI_19") (pintype "passive"))
    )
    (net (code "99") (name "unconnected-(JP2-IO11{slash}SCK-Pad23)") (class "Default")
      (node (ref "JP2") (pin "23") (pinfunction "IO11/SCK_23") (pintype "passive"))
    )
    (net (code "100") (name "unconnected-(JP2-IO12-Pad32)") (class "Default")
      (node (ref "JP2") (pin "32") (pinfunction "IO12_32") (pintype "bidirectional"))
    )
    (net (code "101") (name "unconnected-(JP2-IO13-Pad33)") (class "Default")
      (node (ref "JP2") (pin "33") (pinfunction "IO13_33") (pintype "bidirectional"))
    )
    (net (code "102") (name "unconnected-(JP2-IO16-Pad36)") (class "Default")
      (node (ref "JP2") (pin "36") (pinfunction "IO16_36") (pintype "bidirectional"))
    )
    (net (code "103") (name "unconnected-(JP2-IO17-Pad11)") (class "Default")
      (node (ref "JP2") (pin "11") (pinfunction "IO17_11") (pintype "passive"))
    )
    (net (code "104") (name "unconnected-(JP2-IO19-Pad35)") (class "Default")
      (node (ref "JP2") (pin "35") (pinfunction "IO19_35") (pintype "bidirectional"))
    )
    (net (code "105") (name "unconnected-(JP2-IO20-Pad38)") (class "Default")
      (node (ref "JP2") (pin "38") (pinfunction "IO20_38") (pintype "bidirectional"))
    )
    (net (code "106") (name "unconnected-(JP2-IO21-Pad40)") (class "Default")
      (node (ref "JP2") (pin "40") (pinfunction "IO21_40") (pintype "bidirectional"))
    )
    (net (code "107") (name "unconnected-(JP2-IO22-Pad15)") (class "Default")
      (node (ref "JP2") (pin "15") (pinfunction "IO22_15") (pintype "passive"))
    )
    (net (code "108") (name "unconnected-(JP2-IO23-Pad16)") (class "Default")
      (node (ref "JP2") (pin "16") (pinfunction "IO23_16") (pintype "passive"))
    )
    (net (code "109") (name "unconnected-(JP2-IO24-Pad18)") (class "Default")
      (node (ref "JP2") (pin "18") (pinfunction "IO24_18") (pintype "passive"))
    )
    (net (code "110") (name "unconnected-(JP2-IO25-Pad22)") (class "Default")
      (node (ref "JP2") (pin "22") (pinfunction "IO25_22") (pintype "passive"))
    )
    (net (code "111") (name "unconnected-(JP2-IO26-Pad37)") (class "Default")
      (node (ref "JP2") (pin "37") (pinfunction "IO26_37") (pintype "bidirectional"))
    )
    (net (code "112") (name "unconnected-(JP2-IO27-Pad13)") (class "Default")
      (node (ref "JP2") (pin "13") (pinfunction "IO27_13") (pintype "passive"))
    )
    (net (code "113") (name "unconnected-(JP2-PWM{slash}IO18-Pad12)") (class "Default")
      (node (ref "JP2") (pin "12") (pinfunction "PWM/IO18_12") (pintype "passive"))
    )
    (net (code "114") (name "unconnected-(JP7-Pad6)") (class "Default")
      (node (ref "JP7") (pin "6") (pinfunction "6_6") (pintype "passive"))
    )
    (net (code "115") (name "unconnected-(JP7-Pad8)") (class "Default")
      (node (ref "JP7") (pin "8") (pinfunction "8_8") (pintype "passive"))
    )
  )
)
